# stencil.net
KiCad netlist of a schematic drawn in EAGLE
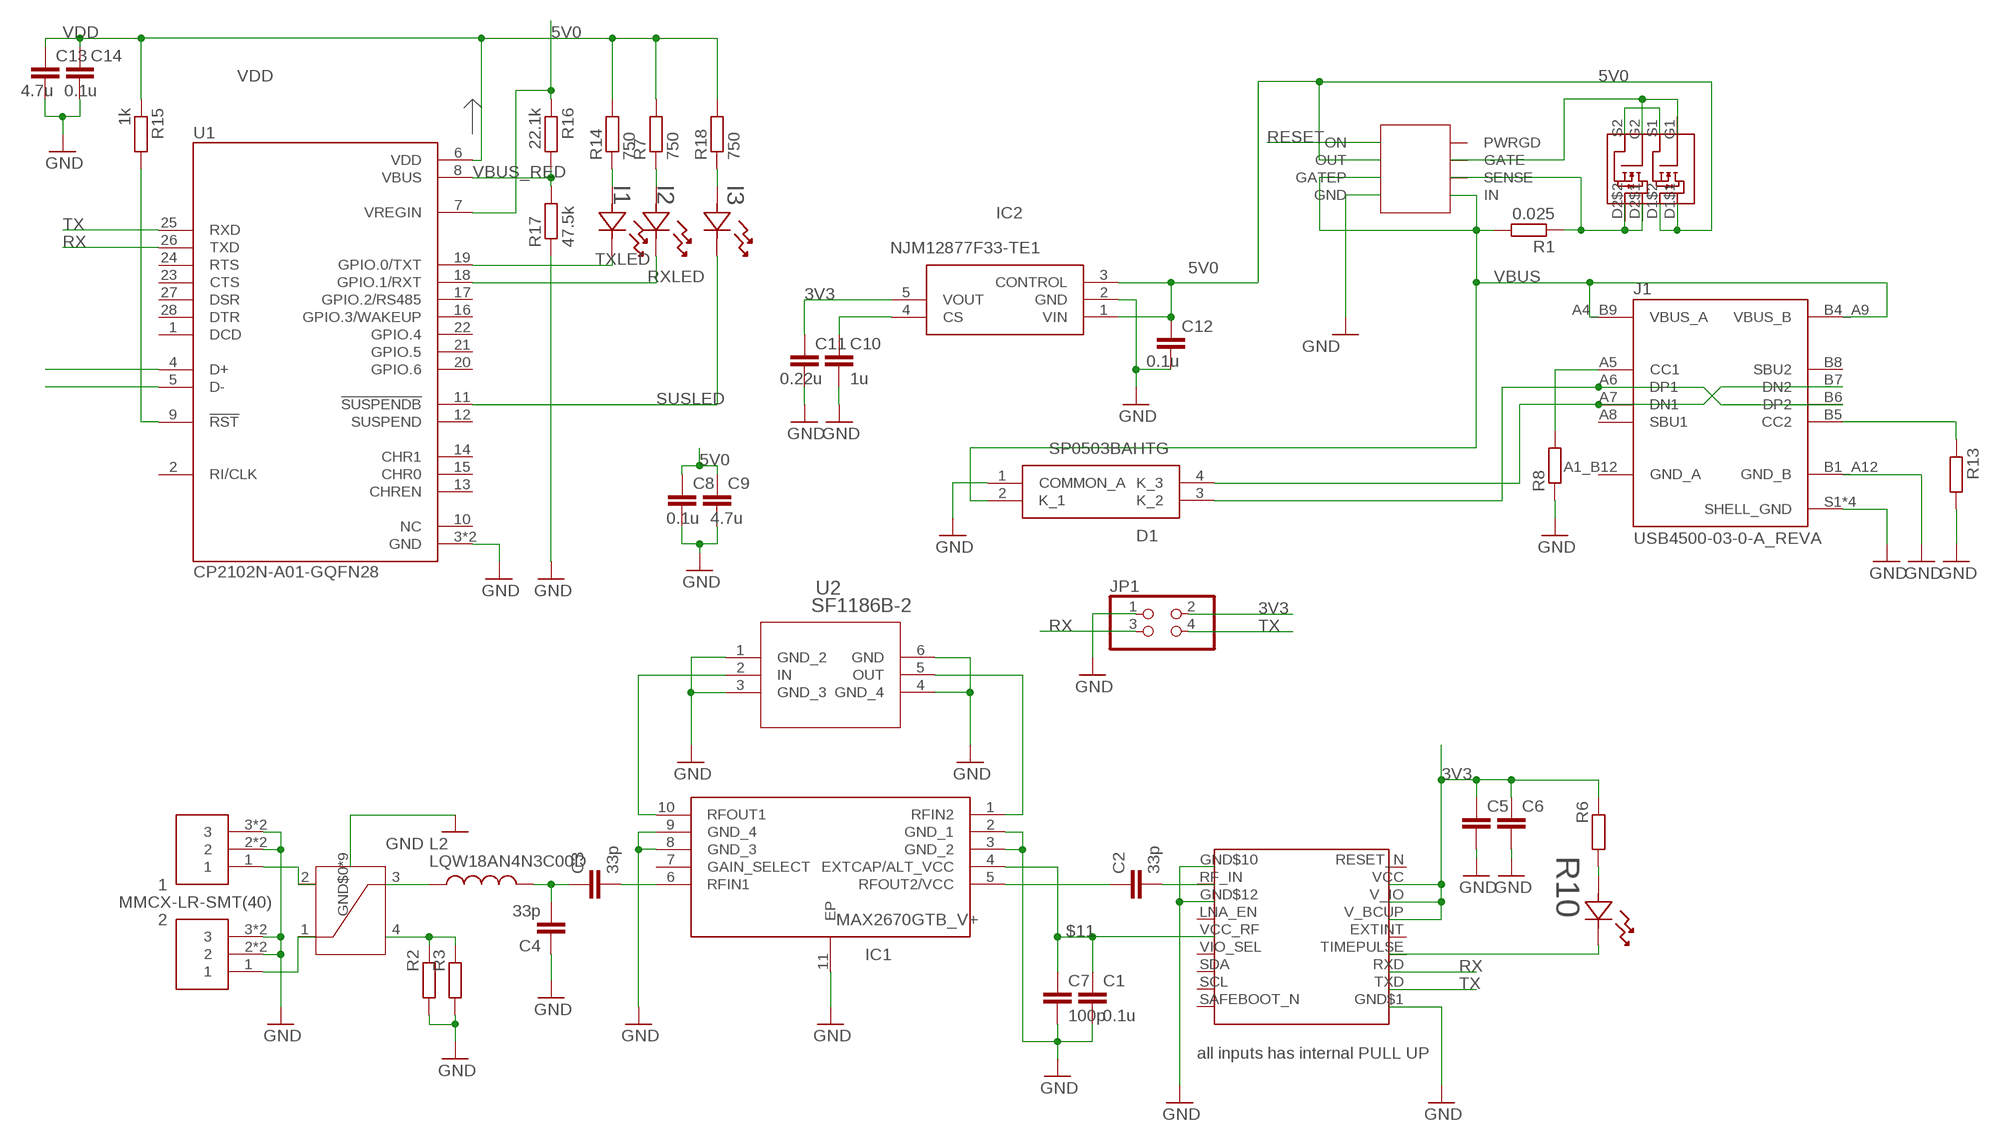
[diagram p0: schematic, sheet 1]
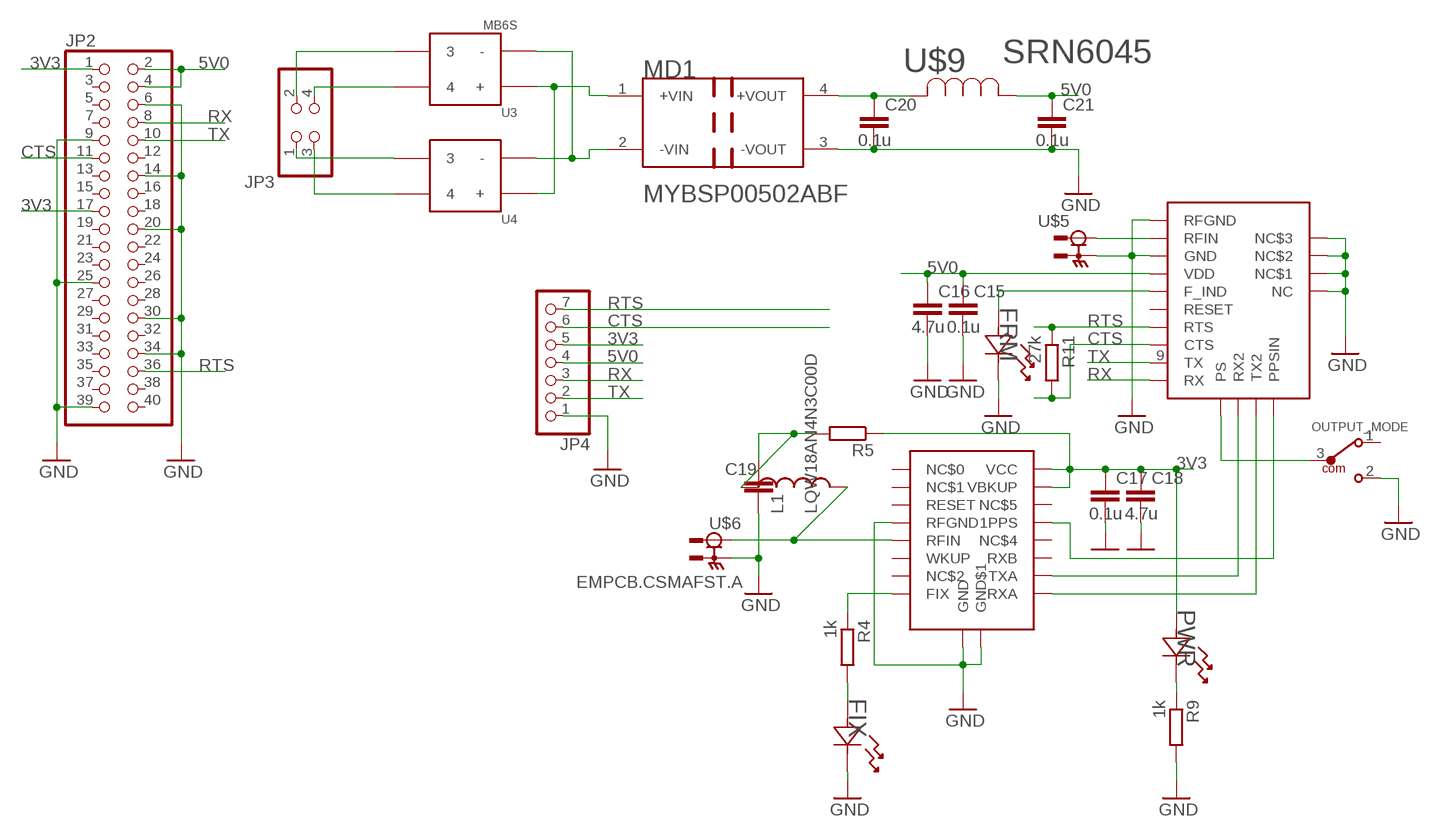
[diagram p1: schematic, sheet 2]

(export (version "E")
  (design (tool "Eeschema 10.0.6"))
  (components
    (comp (ref "C15")
      (value "0.1u")
      (footprint "eagle-import:C1608")
      (libsource (lib "eagle-import") (part "C-EUC1608"))
    )
    (comp (ref "C16")
      (value "4.7u")
      (footprint "eagle-import:C1608")
      (libsource (lib "eagle-import") (part "C-EUC1608"))
    )
    (comp (ref "C17")
      (value "0.1u")
      (footprint "eagle-import:C1608")
      (libsource (lib "eagle-import") (part "C-EUC1608"))
    )
    (comp (ref "C18")
      (value "4.7u")
      (footprint "eagle-import:C1608")
      (libsource (lib "eagle-import") (part "C-EUC1608"))
    )
    (comp (ref "C19")
      (value "C-EUC1608")
      (footprint "eagle-import:C1608")
      (libsource (lib "eagle-import") (part "C-EUC1608"))
    )
    (comp (ref "C20")
      (value "0.1u")
      (footprint "eagle-import:C1608")
      (libsource (lib "eagle-import") (part "C-EUC1608"))
    )
    (comp (ref "C21")
      (value "0.1u")
      (footprint "eagle-import:C1608")
      (libsource (lib "eagle-import") (part "C-EUC1608"))
    )
    (comp (ref "FIX")
      (value "SML-E12P8WT86")
      (footprint "eagle-import:LED_SMLD12_ROM")
      (fields (field (name "COPYRIGHT") "Copyright (C) 2023 Ultra Librarian. All rights reserved."))
      (libsource (lib "eagle-import") (part "SML-E12P8WT86"))
    )
    (comp (ref "FRM")
      (value "SML-E12P8WT86")
      (footprint "eagle-import:LED_SMLD12_ROM")
      (fields (field (name "COPYRIGHT") "Copyright (C) 2023 Ultra Librarian. All rights reserved."))
      (libsource (lib "eagle-import") (part "SML-E12P8WT86"))
    )
    (comp (ref "JP2")
      (value "PINHD-2X20")
      (footprint "eagle-import:2X20")
      (libsource (lib "eagle-import") (part "PINHD-2X20"))
    )
    (comp (ref "JP3")
      (value "PINHD-2X2")
      (footprint "eagle-import:2X02")
      (libsource (lib "eagle-import") (part "PINHD-2X2"))
    )
    (comp (ref "JP4")
      (value "PINHD-1X7/90")
      (footprint "eagle-import:1X07_90")
      (libsource (lib "eagle-import") (part "PINHD-1X7/90"))
    )
    (comp (ref "L1")
      (value "LQW18AN4N3C00D")
      (footprint "eagle-import:INDC1608X100N")
      (fields (field (name "DIGIKEY_PART_NUMBER") "490-6896-2-ND") (field (name "MF") "Murata"))
      (libsource (lib "eagle-import") (part "LQW18AN4N3C00D"))
    )
    (comp (ref "MD1")
      (value "MURATA_MYBSP00502ABFMURATA_MYBSP00502ABF_0_0")
      (footprint "eagle-import:MURATA_MYBSP00502ABF_0")
      (fields (field (name "MF") "Murata Power Solutions Inc.") (field (name "MP") "MYBSP00502ABF"))
      (libsource (lib "eagle-import") (part "MURATA_MYBSP00502ABFMURATA_MYBSP00502ABF_0_0"))
    )
    (comp (ref "OUTPUT_MODE")
      (value "450405020524")
      (footprint "eagle-import:450405020524")
      (libsource (lib "eagle-import") (part "450405020524"))
    )
    (comp (ref "PWR")
      (value "SML-E12P8WT86")
      (footprint "eagle-import:LED_SMLD12_ROM")
      (fields (field (name "COPYRIGHT") "Copyright (C) 2023 Ultra Librarian. All rights reserved."))
      (libsource (lib "eagle-import") (part "SML-E12P8WT86"))
    )
    (comp (ref "R4")
      (value "1k")
      (footprint "eagle-import:R0603")
      (libsource (lib "eagle-import") (part "R-EU_R0603"))
    )
    (comp (ref "R5")
      (value "R-EU_R0603")
      (footprint "eagle-import:R0603")
      (libsource (lib "eagle-import") (part "R-EU_R0603"))
    )
    (comp (ref "R9")
      (value "1k")
      (footprint "eagle-import:R0603")
      (libsource (lib "eagle-import") (part "R-EU_R0603"))
    )
    (comp (ref "R11")
      (value "27k")
      (footprint "eagle-import:R0603_NOSILK")
      (libsource (lib "eagle-import") (part "R-EU_R0603_NOSILK"))
    )
    (comp (ref "U$2")
      (value "GNS5894T")
      (footprint "eagle-import:GNS5XXX")
      (libsource (lib "eagle-import") (part "GNS5894T"))
    )
    (comp (ref "U$4")
      (value "GNS3303")
      (footprint "eagle-import:GNS3303")
      (libsource (lib "eagle-import") (part "GNS3303"))
    )
    (comp (ref "U$5")
      (value "EMPCB.CSMAFST.A")
      (footprint "eagle-import:EMPCB.CSMAFST.A")
      (libsource (lib "eagle-import") (part "EMPCB.CSMAFST.A"))
    )
    (comp (ref "U$6")
      (value "EMPCB.CSMAFST.A")
      (footprint "eagle-import:EMPCB.CSMAFST.A")
      (libsource (lib "eagle-import") (part "EMPCB.CSMAFST.A"))
    )
    (comp (ref "U$9")
      (value "SRN6045")
      (footprint "eagle-import:IND_BOURNS_SRN6045")
      (libsource (lib "eagle-import") (part "SRN6045"))
    )
    (comp (ref "U3")
      (value "MB6S")
      (footprint "eagle-import:SOIC245P670X270-4N")
      (fields (field (name "MF") "onsemi"))
      (libsource (lib "eagle-import") (part "MB6S"))
    )
    (comp (ref "U4")
      (value "MB6S")
      (footprint "eagle-import:SOIC245P670X270-4N")
      (fields (field (name "MF") "onsemi"))
      (libsource (lib "eagle-import") (part "MB6S"))
    )
    (comp (ref "1")
      (value "MMCX-LR-SMT(40)")
      (footprint "eagle-import:MMCX-LR-SMT(40)")
      (libsource (lib "eagle-import") (part "MMCX-LR-SMT(40)"))
    )
    (comp (ref "2")
      (value "MMCX-LR-SMT(40)")
      (footprint "eagle-import:MMCX-LR-SMT(40)")
      (libsource (lib "eagle-import") (part "MMCX-LR-SMT(40)"))
    )
    (comp (ref "C1")
      (value "0.1u")
      (footprint "eagle-import:C1608")
      (libsource (lib "eagle-import") (part "C-EUC1608"))
    )
    (comp (ref "C2")
      (value "33p")
      (footprint "eagle-import:C1608")
      (libsource (lib "eagle-import") (part "C-EUC1608"))
    )
    (comp (ref "C3")
      (value "33p")
      (footprint "eagle-import:C1608")
      (libsource (lib "eagle-import") (part "C-EUC1608"))
    )
    (comp (ref "C4")
      (value "33p")
      (footprint "eagle-import:C1608")
      (libsource (lib "eagle-import") (part "C-EUC1608"))
    )
    (comp (ref "C5")
      (value "C-EUC1608")
      (footprint "eagle-import:C1608")
      (libsource (lib "eagle-import") (part "C-EUC1608"))
    )
    (comp (ref "C6")
      (value "C-EUC1608")
      (footprint "eagle-import:C1608")
      (libsource (lib "eagle-import") (part "C-EUC1608"))
    )
    (comp (ref "C7")
      (value "100p")
      (footprint "eagle-import:C1608")
      (libsource (lib "eagle-import") (part "C-EUC1608"))
    )
    (comp (ref "C8")
      (value "0.1u")
      (footprint "eagle-import:C1608")
      (libsource (lib "eagle-import") (part "C-EUC1608"))
    )
    (comp (ref "C9")
      (value "4.7u")
      (footprint "eagle-import:C1608")
      (libsource (lib "eagle-import") (part "C-EUC1608"))
    )
    (comp (ref "C10")
      (value "1u")
      (footprint "eagle-import:C1608")
      (libsource (lib "eagle-import") (part "C-EUC1608"))
    )
    (comp (ref "C11")
      (value "0.22u")
      (footprint "eagle-import:C1608")
      (libsource (lib "eagle-import") (part "C-EUC1608"))
    )
    (comp (ref "C12")
      (value "0.1u")
      (footprint "eagle-import:C1608")
      (libsource (lib "eagle-import") (part "C-EUC1608"))
    )
    (comp (ref "C13")
      (value "4.7u")
      (footprint "eagle-import:C1608")
      (libsource (lib "eagle-import") (part "C-EUC1608"))
    )
    (comp (ref "C14")
      (value "0.1u")
      (footprint "eagle-import:C1608")
      (libsource (lib "eagle-import") (part "C-EUC1608"))
    )
    (comp (ref "D1")
      (value "SP0503BAHTG")
      (footprint "eagle-import:SP0503BAHTG")
      (fields (field (name "MOUSER_PART_NUMBER") "576-SP0503BAHTG"))
      (libsource (lib "eagle-import") (part "SP0503BAHTG"))
    )
    (comp (ref "I1")
      (value "SML-E12P8WT86")
      (footprint "eagle-import:LED_SMLD12_ROM")
      (fields (field (name "COPYRIGHT") "Copyright (C) 2023 Ultra Librarian. All rights reserved."))
      (libsource (lib "eagle-import") (part "SML-E12P8WT86"))
    )
    (comp (ref "I2")
      (value "SML-E12P8WT86")
      (footprint "eagle-import:LED_SMLD12_ROM")
      (fields (field (name "COPYRIGHT") "Copyright (C) 2023 Ultra Librarian. All rights reserved."))
      (libsource (lib "eagle-import") (part "SML-E12P8WT86"))
    )
    (comp (ref "I3")
      (value "SML-E12P8WT86")
      (footprint "eagle-import:LED_SMLD12_ROM")
      (fields (field (name "COPYRIGHT") "Copyright (C) 2023 Ultra Librarian. All rights reserved."))
      (libsource (lib "eagle-import") (part "SML-E12P8WT86"))
    )
    (comp (ref "IC1")
      (value "MAX2670GTB_V+")
      (footprint "eagle-import:SON50P300X300X80-11N")
      (fields
        (field (name "MANUFACTURER_PART_NUMBER") "MAX2670GTB/V+")
        (field (name "MOUSER_PART_NUMBER") "700-MAX2670GTB/V+")
      )
      (libsource (lib "eagle-import") (part "MAX2670GTB_V+"))
    )
    (comp (ref "IC2")
      (value "NJM12877F33-TE1")
      (footprint "eagle-import:SOT95P280X120-5N")
      (fields (field (name "MOUSER_PART_NUMBER") "513-NJM12877F33-TE1"))
      (libsource (lib "eagle-import") (part "NJM12877F33-TE1"))
    )
    (comp (ref "J1")
      (value "USB4500-03-0-A_REVA")
      (footprint "eagle-import:GCT_USB4500-03-0-A_REVA")
      (fields
        (field (name "DIGI-KEY_PART_NUMBER") "2073-USB4500-03-0-ATR-ND")
        (field (name "MF") "Global Connector Technology")
        (field (name "MP") "USB4500-03-0-A")
      )
      (libsource (lib "eagle-import") (part "USB4500-03-0-A_REVA"))
    )
    (comp (ref "JP1")
      (value "PINHD-2X2")
      (footprint "eagle-import:2X02")
      (libsource (lib "eagle-import") (part "PINHD-2X2"))
    )
    (comp (ref "L2")
      (value "LQW18AN4N3C00D")
      (footprint "eagle-import:INDC1608X100N")
      (fields (field (name "DIGIKEY_PART_NUMBER") "490-6896-2-ND") (field (name "MF") "Murata"))
      (libsource (lib "eagle-import") (part "LQW18AN4N3C00D"))
    )
    (comp (ref "R1")
      (value "0.025")
      (footprint "eagle-import:R0603")
      (libsource (lib "eagle-import") (part "R-EU_R0603"))
    )
    (comp (ref "R2")
      (value "R-EU_R0603")
      (footprint "eagle-import:R0603")
      (libsource (lib "eagle-import") (part "R-EU_R0603"))
    )
    (comp (ref "R3")
      (value "R-EU_R0603")
      (footprint "eagle-import:R0603")
      (libsource (lib "eagle-import") (part "R-EU_R0603"))
    )
    (comp (ref "R6")
      (value "R-EU_R0603")
      (footprint "eagle-import:R0603")
      (libsource (lib "eagle-import") (part "R-EU_R0603"))
    )
    (comp (ref "R7")
      (value "750")
      (footprint "eagle-import:R0603")
      (libsource (lib "eagle-import") (part "R-EU_R0603"))
    )
    (comp (ref "R8")
      (value "R-EU_R0603")
      (footprint "eagle-import:R0603")
      (libsource (lib "eagle-import") (part "R-EU_R0603"))
    )
    (comp (ref "R10")
      (value "SML-E12P8WT86")
      (footprint "eagle-import:LED_SMLD12_ROM")
      (fields (field (name "COPYRIGHT") "Copyright (C) 2023 Ultra Librarian. All rights reserved."))
      (libsource (lib "eagle-import") (part "SML-E12P8WT86"))
    )
    (comp (ref "R13")
      (value "R-EU_R0603")
      (footprint "eagle-import:R0603")
      (libsource (lib "eagle-import") (part "R-EU_R0603"))
    )
    (comp (ref "R14")
      (value "750")
      (footprint "eagle-import:R0603")
      (libsource (lib "eagle-import") (part "R-EU_R0603"))
    )
    (comp (ref "R15")
      (value "1k")
      (footprint "eagle-import:R0603")
      (libsource (lib "eagle-import") (part "R-EU_R0603"))
    )
    (comp (ref "R16")
      (value "22.1k")
      (footprint "eagle-import:R0603")
      (libsource (lib "eagle-import") (part "R-EU_R0603"))
    )
    (comp (ref "R17")
      (value "47.5k")
      (footprint "eagle-import:R0603")
      (libsource (lib "eagle-import") (part "R-EU_R0603"))
    )
    (comp (ref "R18")
      (value "750")
      (footprint "eagle-import:R0603")
      (libsource (lib "eagle-import") (part "R-EU_R0603"))
    )
    (comp (ref "U$1")
      (value "MAX_M10S")
      (footprint "eagle-import:MAX-M10S")
      (libsource (lib "eagle-import") (part "MAX_M10S"))
    )
    (comp (ref "U$3")
      (value "HC125.A")
      (footprint "eagle-import:HC125.A")
      (libsource (lib "eagle-import") (part "HC125.A"))
    )
    (comp (ref "U$7")
      (value "DMG6898LSD")
      (footprint "eagle-import:SOIC127P600X150-8N")
      (libsource (lib "eagle-import") (part "DMG6898LSD"))
    )
    (comp (ref "U$8")
      (value "LTC4361")
      (footprint "eagle-import:SOP65P280X100-8N")
      (libsource (lib "eagle-import") (part "LTC4361"))
    )
    (comp (ref "U1")
      (value "CP2102N-A01-GQFN28")
      (footprint "eagle-import:QFN50P500X500X80-29N")
      (fields (field (name "MF") "Silicon Labs"))
      (libsource (lib "eagle-import") (part "CP2102N-A01-GQFN28"))
    )
    (comp (ref "U2")
      (value "SF1186B-2")
      (footprint "eagle-import:SM3030_MUR")
      (fields (field (name "COPYRIGHT") "Copyright (C) 2023 Ultra Librarian. All rights reserved."))
      (libsource (lib "eagle-import") (part "SF1186B-2"))
    )
  )
  (nets
    (net (code "1") (name "$11") (class "Default")
      (node (ref "C1") (pin "1") (pinfunction "1_1") (pintype "passive"))
      (node (ref "C7") (pin "1") (pinfunction "1_1") (pintype "passive"))
      (node (ref "IC1") (pin "4") (pinfunction "EXTCAP/ALT_VCC_4") (pintype "bidirectional"))
      (node (ref "U$1") (pin "VCC_RF") (pinfunction "VCC_RF_VCC_RF") (pintype "bidirectional"))
    )
    (net (code "2") (name "3V3") (class "Default")
      (node (ref "C11") (pin "1") (pinfunction "1_1") (pintype "passive"))
      (node (ref "C17") (pin "1") (pinfunction "1_1") (pintype "passive"))
      (node (ref "C18") (pin "1") (pinfunction "1_1") (pintype "passive"))
      (node (ref "C5") (pin "1") (pinfunction "1_1") (pintype "passive"))
      (node (ref "C6") (pin "1") (pinfunction "1_1") (pintype "passive"))
      (node (ref "IC2") (pin "5") (pinfunction "VOUT_5") (pintype "bidirectional"))
      (node (ref "JP1") (pin "2") (pinfunction "2_2") (pintype "passive"))
      (node (ref "JP2") (pin "1") (pinfunction "1_1") (pintype "passive"))
      (node (ref "JP2") (pin "17") (pinfunction "17_17") (pintype "passive"))
      (node (ref "JP4") (pin "5") (pinfunction "5_5") (pintype "passive"))
      (node (ref "PWR") (pin "2") (pinfunction "2_2") (pintype "passive"))
      (node (ref "R5") (pin "1") (pinfunction "1_1") (pintype "passive"))
      (node (ref "R6") (pin "2") (pinfunction "2_2") (pintype "passive"))
      (node (ref "U$1") (pin "VCC") (pinfunction "VCC_VCC") (pintype "bidirectional"))
      (node (ref "U$1") (pin "V_BCUP") (pinfunction "V_BCKP_V_BCUP") (pintype "bidirectional"))
      (node (ref "U$1") (pin "V_IO") (pinfunction "V_IO_V_IO") (pintype "bidirectional"))
      (node (ref "U$4") (pin "15") (pinfunction "VBKUP_15") (pintype "bidirectional"))
      (node (ref "U$4") (pin "16") (pinfunction "VCC_16") (pintype "bidirectional"))
    )
    (net (code "3") (name "5V0") (class "Default")
      (node (ref "C12") (pin "1") (pinfunction "1_1") (pintype "passive"))
      (node (ref "C15") (pin "1") (pinfunction "1_1") (pintype "passive"))
      (node (ref "C16") (pin "1") (pinfunction "1_1") (pintype "passive"))
      (node (ref "C21") (pin "1") (pinfunction "1_1") (pintype "passive"))
      (node (ref "C8") (pin "1") (pinfunction "1_1") (pintype "passive"))
      (node (ref "C9") (pin "1") (pinfunction "1_1") (pintype "passive"))
      (node (ref "IC2") (pin "1") (pinfunction "VIN_1") (pintype "bidirectional"))
      (node (ref "IC2") (pin "3") (pinfunction "CONTROL_3") (pintype "bidirectional"))
      (node (ref "JP2") (pin "2") (pinfunction "2_2") (pintype "passive"))
      (node (ref "JP2") (pin "4") (pinfunction "4_4") (pintype "passive"))
      (node (ref "JP4") (pin "4") (pinfunction "4_4") (pintype "passive"))
      (node (ref "R16") (pin "1") (pinfunction "1_1") (pintype "passive"))
      (node (ref "U$2") (pin "4") (pinfunction "VDD_4") (pintype "bidirectional"))
      (node (ref "U$7") (pin "D1$1") (pinfunction "D1$1_D1$1") (pintype "bidirectional"))
      (node (ref "U$7") (pin "D1$2") (pinfunction "D1$2_D1$2") (pintype "bidirectional"))
      (node (ref "U$8") (pin "OUT") (pinfunction "OUT_OUT") (pintype "bidirectional"))
      (node (ref "U$9") (pin "1") (pinfunction "1_1") (pintype "passive"))
      (node (ref "U1") (pin "7") (pinfunction "VREGIN_7") (pintype "power_in"))
    )
    (net (code "4") (name "CTS") (class "Default")
      (node (ref "JP2") (pin "11") (pinfunction "11_11") (pintype "passive"))
      (node (ref "JP4") (pin "6") (pinfunction "6_6") (pintype "passive"))
      (node (ref "R11") (pin "2") (pinfunction "2_2") (pintype "passive"))
      (node (ref "U$2") (pin "8") (pinfunction "CTS_8") (pintype "bidirectional"))
    )
    (net (code "5") (name "D+") (class "Default")
      (node (ref "D1") (pin "3") (pinfunction "K_2_3") (pintype "bidirectional"))
      (node (ref "J1") (pin "A6") (pinfunction "DP1_A6") (pintype "bidirectional"))
      (node (ref "J1") (pin "B6") (pinfunction "DP2_B6") (pintype "bidirectional"))
      (node (ref "U1") (pin "4") (pinfunction "D+_4") (pintype "bidirectional"))
    )
    (net (code "6") (name "D-") (class "Default")
      (node (ref "D1") (pin "4") (pinfunction "K_3_4") (pintype "bidirectional"))
      (node (ref "J1") (pin "A7") (pinfunction "DN1_A7") (pintype "bidirectional"))
      (node (ref "J1") (pin "B7") (pinfunction "DN2_B7") (pintype "bidirectional"))
      (node (ref "U1") (pin "5") (pinfunction "D-_5") (pintype "bidirectional"))
    )
    (net (code "7") (name "GND") (class "Default")
      (node (ref "1") (pin "2") (pinfunction "2_2") (pintype "bidirectional"))
      (node (ref "1") (pin "3") (pinfunction "3_3") (pintype "bidirectional"))
      (node (ref "1") (pin "4") (pinfunction "2_4") (pintype "bidirectional"))
      (node (ref "1") (pin "5") (pinfunction "3_5") (pintype "bidirectional"))
      (node (ref "2") (pin "2") (pinfunction "2_2") (pintype "bidirectional"))
      (node (ref "2") (pin "3") (pinfunction "3_3") (pintype "bidirectional"))
      (node (ref "2") (pin "4") (pinfunction "2_4") (pintype "bidirectional"))
      (node (ref "2") (pin "5") (pinfunction "3_5") (pintype "bidirectional"))
      (node (ref "C1") (pin "2") (pinfunction "2_2") (pintype "passive"))
      (node (ref "C10") (pin "2") (pinfunction "2_2") (pintype "passive"))
      (node (ref "C11") (pin "2") (pinfunction "2_2") (pintype "passive"))
      (node (ref "C12") (pin "2") (pinfunction "2_2") (pintype "passive"))
      (node (ref "C13") (pin "2") (pinfunction "2_2") (pintype "passive"))
      (node (ref "C14") (pin "2") (pinfunction "2_2") (pintype "passive"))
      (node (ref "C15") (pin "2") (pinfunction "2_2") (pintype "passive"))
      (node (ref "C16") (pin "2") (pinfunction "2_2") (pintype "passive"))
      (node (ref "C17") (pin "2") (pinfunction "2_2") (pintype "passive"))
      (node (ref "C18") (pin "2") (pinfunction "2_2") (pintype "passive"))
      (node (ref "C19") (pin "2") (pinfunction "2_2") (pintype "passive"))
      (node (ref "C20") (pin "2") (pinfunction "2_2") (pintype "passive"))
      (node (ref "C21") (pin "2") (pinfunction "2_2") (pintype "passive"))
      (node (ref "C4") (pin "1") (pinfunction "1_1") (pintype "passive"))
      (node (ref "C5") (pin "2") (pinfunction "2_2") (pintype "passive"))
      (node (ref "C6") (pin "2") (pinfunction "2_2") (pintype "passive"))
      (node (ref "C7") (pin "2") (pinfunction "2_2") (pintype "passive"))
      (node (ref "C8") (pin "2") (pinfunction "2_2") (pintype "passive"))
      (node (ref "C9") (pin "2") (pinfunction "2_2") (pintype "passive"))
      (node (ref "D1") (pin "1") (pinfunction "COMMON_A_1") (pintype "bidirectional"))
      (node (ref "FIX") (pin "1") (pinfunction "1_1") (pintype "passive"))
      (node (ref "FRM") (pin "1") (pinfunction "1_1") (pintype "passive"))
      (node (ref "IC1") (pin "11") (pinfunction "EP_11") (pintype "bidirectional"))
      (node (ref "IC1") (pin "2") (pinfunction "GND_1_2") (pintype "bidirectional"))
      (node (ref "IC1") (pin "3") (pinfunction "GND_2_3") (pintype "bidirectional"))
      (node (ref "IC1") (pin "8") (pinfunction "GND_3_8") (pintype "bidirectional"))
      (node (ref "IC1") (pin "9") (pinfunction "GND_4_9") (pintype "bidirectional"))
      (node (ref "IC2") (pin "2") (pinfunction "GND_2") (pintype "bidirectional"))
      (node (ref "J1") (pin "B1_A12") (pinfunction "GND_B_B1_A12") (pintype "power_in"))
      (node (ref "J1") (pin "S1") (pinfunction "SHELL_GND_S1") (pintype "power_in"))
      (node (ref "J1") (pin "S2") (pinfunction "SHELL_GND_S2") (pintype "power_in"))
      (node (ref "J1") (pin "S3") (pinfunction "SHELL_GND_S3") (pintype "power_in"))
      (node (ref "J1") (pin "S4") (pinfunction "SHELL_GND_S4") (pintype "power_in"))
      (node (ref "JP1") (pin "1") (pinfunction "1_1") (pintype "passive"))
      (node (ref "JP2") (pin "14") (pinfunction "14_14") (pintype "passive"))
      (node (ref "JP2") (pin "20") (pinfunction "20_20") (pintype "passive"))
      (node (ref "JP2") (pin "25") (pinfunction "25_25") (pintype "passive"))
      (node (ref "JP2") (pin "30") (pinfunction "30_30") (pintype "passive"))
      (node (ref "JP2") (pin "34") (pinfunction "34_34") (pintype "passive"))
      (node (ref "JP2") (pin "39") (pinfunction "39_39") (pintype "passive"))
      (node (ref "JP2") (pin "6") (pinfunction "6_6") (pintype "passive"))
      (node (ref "JP2") (pin "9") (pinfunction "9_9") (pintype "passive"))
      (node (ref "JP4") (pin "1") (pinfunction "1_1") (pintype "passive"))
      (node (ref "MD1") (pin "3") (pinfunction "-VOUT_3") (pintype "power_in"))
      (node (ref "OUTPUT_MODE") (pin "2") (pinfunction "3_2") (pintype "passive"))
      (node (ref "R13") (pin "2") (pinfunction "2_2") (pintype "passive"))
      (node (ref "R17") (pin "1") (pinfunction "1_1") (pintype "passive"))
      (node (ref "R2") (pin "1") (pinfunction "1_1") (pintype "passive"))
      (node (ref "R3") (pin "1") (pinfunction "1_1") (pintype "passive"))
      (node (ref "R8") (pin "1") (pinfunction "1_1") (pintype "passive"))
      (node (ref "R9") (pin "2") (pinfunction "2_2") (pintype "passive"))
      (node (ref "U$1") (pin "GND$1") (pinfunction "GND$1_GND$1") (pintype "bidirectional"))
      (node (ref "U$1") (pin "GND$10") (pinfunction "GND$10_GND$10") (pintype "bidirectional"))
      (node (ref "U$1") (pin "GND$12") (pinfunction "GND$12_GND$12") (pintype "bidirectional"))
      (node (ref "U$2") (pin "1") (pinfunction "RFGND_1") (pintype "bidirectional"))
      (node (ref "U$2") (pin "15") (pinfunction "NC_15") (pintype "bidirectional"))
      (node (ref "U$2") (pin "16") (pinfunction "NC$1_16") (pintype "bidirectional"))
      (node (ref "U$2") (pin "17") (pinfunction "NC$2_17") (pintype "bidirectional"))
      (node (ref "U$2") (pin "18") (pinfunction "NC$3_18") (pintype "bidirectional"))
      (node (ref "U$2") (pin "3") (pinfunction "GND_3") (pintype "bidirectional"))
      (node (ref "U$3") (pin "GND$0") (pinfunction "GND_GND$0") (pintype "bidirectional"))
      (node (ref "U$3") (pin "GND$1") (pinfunction "GND_GND$1") (pintype "bidirectional"))
      (node (ref "U$3") (pin "GND$2") (pinfunction "GND_GND$2") (pintype "bidirectional"))
      (node (ref "U$3") (pin "GND$3") (pinfunction "GND_GND$3") (pintype "bidirectional"))
      (node (ref "U$3") (pin "GND$4") (pinfunction "GND_GND$4") (pintype "bidirectional"))
      (node (ref "U$3") (pin "GND$5") (pinfunction "GND_GND$5") (pintype "bidirectional"))
      (node (ref "U$3") (pin "GND$6") (pinfunction "GND_GND$6") (pintype "bidirectional"))
      (node (ref "U$3") (pin "GND$7") (pinfunction "GND_GND$7") (pintype "bidirectional"))
      (node (ref "U$3") (pin "GND$8") (pinfunction "GND_GND$8") (pintype "bidirectional"))
      (node (ref "U$4") (pin "4") (pinfunction "RFGND_4") (pintype "bidirectional"))
      (node (ref "U$4") (pin "E1") (pinfunction "GND_E1") (pintype "bidirectional"))
      (node (ref "U$4") (pin "E2") (pinfunction "GND$1_E2") (pintype "bidirectional"))
      (node (ref "U$5") (pin "GND$0") (pinfunction "2_GND$0") (pintype "passive"))
      (node (ref "U$5") (pin "GND$1") (pinfunction "2_GND$1") (pintype "passive"))
      (node (ref "U$5") (pin "GND$2") (pinfunction "2_GND$2") (pintype "passive"))
      (node (ref "U$5") (pin "GND$3") (pinfunction "2_GND$3") (pintype "passive"))
      (node (ref "U$6") (pin "GND$0") (pinfunction "2_GND$0") (pintype "passive"))
      (node (ref "U$6") (pin "GND$1") (pinfunction "2_GND$1") (pintype "passive"))
      (node (ref "U$6") (pin "GND$2") (pinfunction "2_GND$2") (pintype "passive"))
      (node (ref "U$6") (pin "GND$3") (pinfunction "2_GND$3") (pintype "passive"))
      (node (ref "U$8") (pin "GND") (pinfunction "GND_GND") (pintype "bidirectional"))
      (node (ref "U1") (pin "29") (pinfunction "GND_29") (pintype "power_in"))
      (node (ref "U1") (pin "3") (pinfunction "GND_3") (pintype "power_in"))
      (node (ref "U2") (pin "1") (pinfunction "GND_2_1") (pintype "passive"))
      (node (ref "U2") (pin "3") (pinfunction "GND_3_3") (pintype "passive"))
      (node (ref "U2") (pin "4") (pinfunction "GND_4_4") (pintype "passive"))
      (node (ref "U2") (pin "6") (pinfunction "GND_6") (pintype "passive"))
    )
    (net (code "8") (name "GND_A") (class "Default")
      (node (ref "J1") (pin "A1_B12") (pinfunction "GND_A_A1_B12") (pintype "power_in"))
    )
    (net (code "9") (name "Net-(1-Pad1)") (class "Default")
      (node (ref "1") (pin "1") (pinfunction "1_1") (pintype "bidirectional"))
      (node (ref "U$3") (pin "2") (pinfunction "2_2") (pintype "bidirectional"))
    )
    (net (code "10") (name "Net-(2-Pad1)") (class "Default")
      (node (ref "2") (pin "1") (pinfunction "1_1") (pintype "bidirectional"))
      (node (ref "U$3") (pin "1") (pinfunction "1_1") (pintype "bidirectional"))
    )
    (net (code "11") (name "Net-(C2-Pad2)") (class "Default")
      (node (ref "C2") (pin "2") (pinfunction "2_2") (pintype "passive"))
      (node (ref "U$1") (pin "RF_IN") (pinfunction "RF_IN_RF_IN") (pintype "bidirectional"))
    )
    (net (code "12") (name "Net-(C3-Pad1)") (class "Default")
      (node (ref "C3") (pin "1") (pinfunction "1_1") (pintype "passive"))
      (node (ref "C4") (pin "2") (pinfunction "2_2") (pintype "passive"))
      (node (ref "L2") (pin "2") (pinfunction "2_2") (pintype "passive"))
    )
    (net (code "13") (name "Net-(C19-Pad1)") (class "Default")
      (node (ref "C19") (pin "1") (pinfunction "1_1") (pintype "passive"))
      (node (ref "L1") (pin "1") (pinfunction "1_1") (pintype "passive"))
      (node (ref "R5") (pin "2") (pinfunction "2_2") (pintype "passive"))
    )
    (net (code "14") (name "Net-(FIX-Pad2)") (class "Default")
      (node (ref "FIX") (pin "2") (pinfunction "2_2") (pintype "passive"))
      (node (ref "R4") (pin "2") (pinfunction "2_2") (pintype "passive"))
    )
    (net (code "15") (name "Net-(I1-Pad2)") (class "Default")
      (node (ref "I1") (pin "2") (pinfunction "2_2") (pintype "passive"))
      (node (ref "R14") (pin "1") (pinfunction "1_1") (pintype "passive"))
    )
    (net (code "16") (name "Net-(I2-Pad2)") (class "Default")
      (node (ref "I2") (pin "2") (pinfunction "2_2") (pintype "passive"))
      (node (ref "R7") (pin "1") (pinfunction "1_1") (pintype "passive"))
    )
    (net (code "17") (name "Net-(I3-Pad2)") (class "Default")
      (node (ref "I3") (pin "2") (pinfunction "2_2") (pintype "passive"))
      (node (ref "R18") (pin "1") (pinfunction "1_1") (pintype "passive"))
    )
    (net (code "18") (name "Net-(IC1-RFIN1)") (class "Default")
      (node (ref "C3") (pin "2") (pinfunction "2_2") (pintype "passive"))
      (node (ref "IC1") (pin "6") (pinfunction "RFIN1_6") (pintype "bidirectional"))
    )
    (net (code "19") (name "Net-(IC1-RFIN2)") (class "Default")
      (node (ref "IC1") (pin "1") (pinfunction "RFIN2_1") (pintype "bidirectional"))
      (node (ref "U2") (pin "5") (pinfunction "OUT_5") (pintype "output"))
    )
    (net (code "20") (name "Net-(IC1-RFOUT1)") (class "Default")
      (node (ref "IC1") (pin "10") (pinfunction "RFOUT1_10") (pintype "bidirectional"))
      (node (ref "U2") (pin "2") (pinfunction "IN_2") (pintype "input"))
    )
    (net (code "21") (name "Net-(IC1-RFOUT2{slash}VCC)") (class "Default")
      (node (ref "C2") (pin "1") (pinfunction "1_1") (pintype "passive"))
      (node (ref "IC1") (pin "5") (pinfunction "RFOUT2/VCC_5") (pintype "bidirectional"))
    )
    (net (code "22") (name "Net-(IC2-CS)") (class "Default")
      (node (ref "C10") (pin "1") (pinfunction "1_1") (pintype "passive"))
      (node (ref "IC2") (pin "4") (pinfunction "CS_4") (pintype "bidirectional"))
    )
    (net (code "23") (name "Net-(J1-CC1)") (class "Default")
      (node (ref "J1") (pin "A5") (pinfunction "CC1_A5") (pintype "bidirectional"))
      (node (ref "R8") (pin "2") (pinfunction "2_2") (pintype "passive"))
    )
    (net (code "24") (name "Net-(J1-CC2)") (class "Default")
      (node (ref "J1") (pin "B5") (pinfunction "CC2_B5") (pintype "bidirectional"))
      (node (ref "R13") (pin "1") (pinfunction "1_1") (pintype "passive"))
    )
    (net (code "25") (name "Net-(JP3-Pad1)") (class "Default")
      (node (ref "JP3") (pin "1") (pinfunction "1_1") (pintype "passive"))
      (node (ref "U4") (pin "3") (pinfunction "3_3") (pintype "output"))
    )
    (net (code "26") (name "Net-(JP3-Pad2)") (class "Default")
      (node (ref "JP3") (pin "2") (pinfunction "2_2") (pintype "passive"))
      (node (ref "U3") (pin "3") (pinfunction "3_3") (pintype "output"))
    )
    (net (code "27") (name "Net-(JP3-Pad3)") (class "Default")
      (node (ref "JP3") (pin "3") (pinfunction "3_3") (pintype "passive"))
      (node (ref "U4") (pin "4") (pinfunction "4_4") (pintype "output"))
    )
    (net (code "28") (name "Net-(JP3-Pad4)") (class "Default")
      (node (ref "JP3") (pin "4") (pinfunction "4_4") (pintype "passive"))
      (node (ref "U3") (pin "4") (pinfunction "4_4") (pintype "output"))
    )
    (net (code "29") (name "Net-(L2-Pad1)") (class "Default")
      (node (ref "L2") (pin "1") (pinfunction "1_1") (pintype "passive"))
      (node (ref "U$3") (pin "3") (pinfunction "3_3") (pintype "bidirectional"))
    )
    (net (code "30") (name "Net-(MD1-+VIN)") (class "Default")
      (node (ref "MD1") (pin "1") (pinfunction "+VIN_1") (pintype "power_in"))
      (node (ref "U3") (pin "1") (pinfunction "+_1") (pintype "input"))
      (node (ref "U4") (pin "1") (pinfunction "+_1") (pintype "input"))
    )
    (net (code "31") (name "Net-(MD1-+VOUT)") (class "Default")
      (node (ref "C20") (pin "1") (pinfunction "1_1") (pintype "passive"))
      (node (ref "MD1") (pin "4") (pinfunction "+VOUT_4") (pintype "power_in"))
      (node (ref "U$9") (pin "2") (pinfunction "2_2") (pintype "passive"))
    )
    (net (code "32") (name "Net-(MD1--VIN)") (class "Default")
      (node (ref "MD1") (pin "2") (pinfunction "-VIN_2") (pintype "power_in"))
      (node (ref "U3") (pin "2") (pinfunction "-_2") (pintype "input"))
      (node (ref "U4") (pin "2") (pinfunction "-_2") (pintype "input"))
    )
    (net (code "33") (name "Net-(OUTPUT_MODE-2)") (class "Default")
      (node (ref "OUTPUT_MODE") (pin "3") (pinfunction "2_3") (pintype "passive"))
      (node (ref "U$2") (pin "11") (pinfunction "PS_11") (pintype "bidirectional"))
    )
    (net (code "34") (name "Net-(PWR-Pad1)") (class "Default")
      (node (ref "PWR") (pin "1") (pinfunction "1_1") (pintype "passive"))
      (node (ref "R9") (pin "1") (pinfunction "1_1") (pintype "passive"))
    )
    (net (code "35") (name "Net-(R1-Pad1)") (class "Default")
      (node (ref "R1") (pin "1") (pinfunction "1_1") (pintype "passive"))
      (node (ref "U$7") (pin "D2$1") (pinfunction "D2$1_D2$1") (pintype "bidirectional"))
      (node (ref "U$7") (pin "D2$2") (pinfunction "D2$2_D2$2") (pintype "bidirectional"))
      (node (ref "U$8") (pin "SENSE") (pinfunction "SENSE_SENSE") (pintype "bidirectional"))
    )
    (net (code "36") (name "Net-(R2-Pad2)") (class "Default")
      (node (ref "R2") (pin "2") (pinfunction "2_2") (pintype "passive"))
      (node (ref "R3") (pin "2") (pinfunction "2_2") (pintype "passive"))
      (node (ref "U$3") (pin "4") (pinfunction "4_4") (pintype "bidirectional"))
    )
    (net (code "37") (name "Net-(R10-Pad1)") (class "Default")
      (node (ref "R10") (pin "1") (pinfunction "1_1") (pintype "passive"))
      (node (ref "U$1") (pin "TIMEPULSE") (pinfunction "TIMEPULSE_TIMEPULSE") (pintype "bidirectional"))
    )
    (net (code "38") (name "Net-(R10-Pad2)") (class "Default")
      (node (ref "R10") (pin "2") (pinfunction "2_2") (pintype "passive"))
      (node (ref "R6") (pin "1") (pinfunction "1_1") (pintype "passive"))
    )
    (net (code "39") (name "Net-(U$2-F_IND)") (class "Default")
      (node (ref "FRM") (pin "2") (pinfunction "2_2") (pintype "passive"))
      (node (ref "U$2") (pin "5") (pinfunction "F_IND_5") (pintype "bidirectional"))
    )
    (net (code "40") (name "Net-(U$2-PPSIN)") (class "Default")
      (node (ref "U$2") (pin "14") (pinfunction "PPSIN_14") (pintype "bidirectional"))
      (node (ref "U$4") (pin "13") (pinfunction "1PPS_13") (pintype "bidirectional"))
    )
    (net (code "41") (name "Net-(U$2-RFIN)") (class "Default")
      (node (ref "U$2") (pin "2") (pinfunction "RFIN_2") (pintype "bidirectional"))
      (node (ref "U$5") (pin "RF") (pinfunction "1_RF") (pintype "passive"))
    )
    (net (code "42") (name "Net-(U$2-RX2)") (class "Default")
      (node (ref "U$2") (pin "12") (pinfunction "RX2_12") (pintype "bidirectional"))
      (node (ref "U$4") (pin "10") (pinfunction "TXA_10") (pintype "bidirectional"))
    )
    (net (code "43") (name "Net-(U$2-TX2)") (class "Default")
      (node (ref "U$2") (pin "13") (pinfunction "TX2_13") (pintype "bidirectional"))
      (node (ref "U$4") (pin "9") (pinfunction "RXA_9") (pintype "bidirectional"))
    )
    (net (code "44") (name "Net-(U$4-FIX)") (class "Default")
      (node (ref "R4") (pin "1") (pinfunction "1_1") (pintype "passive"))
      (node (ref "U$4") (pin "8") (pinfunction "FIX_8") (pintype "bidirectional"))
    )
    (net (code "45") (name "Net-(U$4-RFIN)") (class "Default")
      (node (ref "L1") (pin "2") (pinfunction "2_2") (pintype "passive"))
      (node (ref "U$4") (pin "5") (pinfunction "RFIN_5") (pintype "bidirectional"))
      (node (ref "U$6") (pin "RF") (pinfunction "1_RF") (pintype "passive"))
    )
    (net (code "46") (name "Net-(U$7-PadG1)") (class "Default")
      (node (ref "U$7") (pin "G1") (pinfunction "G1_G1") (pintype "bidirectional"))
      (node (ref "U$7") (pin "G2") (pinfunction "G2_G2") (pintype "bidirectional"))
      (node (ref "U$8") (pin "GATE") (pinfunction "GATE_GATE") (pintype "bidirectional"))
    )
    (net (code "47") (name "Net-(U$7-PadS1)") (class "Default")
      (node (ref "U$7") (pin "S1") (pinfunction "S1_S1") (pintype "bidirectional"))
      (node (ref "U$7") (pin "S2") (pinfunction "S2_S2") (pintype "bidirectional"))
    )
    (net (code "48") (name "Net-(U1-~{RST})") (class "Default")
      (node (ref "R15") (pin "2") (pinfunction "2_2") (pintype "passive"))
      (node (ref "U1") (pin "9") (pinfunction "~{RST}_9") (pintype "input"))
    )
    (net (code "49") (name "RESET") (class "Default")
      (node (ref "U$8") (pin "ON") (pinfunction "ON_ON") (pintype "bidirectional"))
    )
    (net (code "50") (name "RTS") (class "Default")
      (node (ref "JP2") (pin "36") (pinfunction "36_36") (pintype "passive"))
      (node (ref "JP4") (pin "7") (pinfunction "7_7") (pintype "passive"))
      (node (ref "R11") (pin "1") (pinfunction "1_1") (pintype "passive"))
      (node (ref "U$2") (pin "7") (pinfunction "RTS_7") (pintype "bidirectional"))
    )
    (net (code "51") (name "RX") (class "Default")
      (node (ref "JP1") (pin "3") (pinfunction "3_3") (pintype "passive"))
      (node (ref "JP2") (pin "8") (pinfunction "8_8") (pintype "passive"))
      (node (ref "JP4") (pin "3") (pinfunction "3_3") (pintype "passive"))
      (node (ref "U$1") (pin "RXD") (pinfunction "RXD_RXD") (pintype "bidirectional"))
      (node (ref "U$2") (pin "10") (pinfunction "RX_10") (pintype "bidirectional"))
      (node (ref "U1") (pin "26") (pinfunction "TXD_26") (pintype "output"))
    )
    (net (code "52") (name "RXLED") (class "Default")
      (node (ref "I2") (pin "1") (pinfunction "1_1") (pintype "passive"))
      (node (ref "U1") (pin "18") (pinfunction "GPIO.1/RXT_18") (pintype "bidirectional"))
    )
    (net (code "53") (name "SUSLED") (class "Default")
      (node (ref "I3") (pin "1") (pinfunction "1_1") (pintype "passive"))
      (node (ref "U1") (pin "11") (pinfunction "~{SUSPENDB}_11") (pintype "output"))
    )
    (net (code "54") (name "TX") (class "Default")
      (node (ref "JP1") (pin "4") (pinfunction "4_4") (pintype "passive"))
      (node (ref "JP2") (pin "10") (pinfunction "10_10") (pintype "passive"))
      (node (ref "JP4") (pin "2") (pinfunction "2_2") (pintype "passive"))
      (node (ref "U$1") (pin "TXD") (pinfunction "TXD_TXD") (pintype "bidirectional"))
      (node (ref "U$2") (pin "9") (pinfunction "TX_9") (pintype "bidirectional"))
      (node (ref "U1") (pin "25") (pinfunction "RXD_25") (pintype "input"))
    )
    (net (code "55") (name "TXLED") (class "Default")
      (node (ref "I1") (pin "1") (pinfunction "1_1") (pintype "passive"))
      (node (ref "U1") (pin "19") (pinfunction "GPIO.0/TXT_19") (pintype "bidirectional"))
    )
    (net (code "56") (name "VBUS") (class "Default")
      (node (ref "D1") (pin "2") (pinfunction "K_1_2") (pintype "bidirectional"))
      (node (ref "J1") (pin "A4_B9") (pinfunction "VBUS_A_A4_B9") (pintype "power_in"))
      (node (ref "J1") (pin "B4_A9") (pinfunction "VBUS_B_B4_A9") (pintype "power_in"))
      (node (ref "R1") (pin "2") (pinfunction "2_2") (pintype "passive"))
      (node (ref "U$8") (pin "GATEP") (pinfunction "GATEP_GATEP") (pintype "bidirectional"))
      (node (ref "U$8") (pin "IN") (pinfunction "IN_IN") (pintype "bidirectional"))
    )
    (net (code "57") (name "VBUS_RED") (class "Default")
      (node (ref "R16") (pin "2") (pinfunction "2_2") (pintype "passive"))
      (node (ref "R17") (pin "2") (pinfunction "2_2") (pintype "passive"))
      (node (ref "U1") (pin "8") (pinfunction "VBUS_8") (pintype "power_in"))
    )
    (net (code "58") (name "VDD") (class "Default")
      (node (ref "C13") (pin "1") (pinfunction "1_1") (pintype "passive"))
      (node (ref "C14") (pin "1") (pinfunction "1_1") (pintype "passive"))
      (node (ref "R14") (pin "2") (pinfunction "2_2") (pintype "passive"))
      (node (ref "R15") (pin "1") (pinfunction "1_1") (pintype "passive"))
      (node (ref "R18") (pin "2") (pinfunction "2_2") (pintype "passive"))
      (node (ref "R7") (pin "2") (pinfunction "2_2") (pintype "passive"))
      (node (ref "U1") (pin "6") (pinfunction "VDD_6") (pintype "power_in"))
    )
    (net (code "59") (name "unconnected-(IC1-GAIN_SELECT-Pad7)") (class "Default")
      (node (ref "IC1") (pin "7") (pinfunction "GAIN_SELECT_7") (pintype "bidirectional"))
    )
    (net (code "60") (name "unconnected-(J1-SBU1-PadA8)") (class "Default")
      (node (ref "J1") (pin "A8") (pinfunction "SBU1_A8") (pintype "bidirectional"))
    )
    (net (code "61") (name "unconnected-(J1-SBU2-PadB8)") (class "Default")
      (node (ref "J1") (pin "B8") (pinfunction "SBU2_B8") (pintype "bidirectional"))
    )
    (net (code "62") (name "unconnected-(JP2-Pad3)") (class "Default")
      (node (ref "JP2") (pin "3") (pinfunction "3_3") (pintype "passive"))
    )
    (net (code "63") (name "unconnected-(JP2-Pad5)") (class "Default")
      (node (ref "JP2") (pin "5") (pinfunction "5_5") (pintype "passive"))
    )
    (net (code "64") (name "unconnected-(JP2-Pad7)") (class "Default")
      (node (ref "JP2") (pin "7") (pinfunction "7_7") (pintype "passive"))
    )
    (net (code "65") (name "unconnected-(JP2-Pad12)") (class "Default")
      (node (ref "JP2") (pin "12") (pinfunction "12_12") (pintype "passive"))
    )
    (net (code "66") (name "unconnected-(JP2-Pad13)") (class "Default")
      (node (ref "JP2") (pin "13") (pinfunction "13_13") (pintype "passive"))
    )
    (net (code "67") (name "unconnected-(JP2-Pad15)") (class "Default")
      (node (ref "JP2") (pin "15") (pinfunction "15_15") (pintype "passive"))
    )
    (net (code "68") (name "unconnected-(JP2-Pad16)") (class "Default")
      (node (ref "JP2") (pin "16") (pinfunction "16_16") (pintype "passive"))
    )
    (net (code "69") (name "unconnected-(JP2-Pad18)") (class "Default")
      (node (ref "JP2") (pin "18") (pinfunction "18_18") (pintype "passive"))
    )
    (net (code "70") (name "unconnected-(JP2-Pad19)") (class "Default")
      (node (ref "JP2") (pin "19") (pinfunction "19_19") (pintype "passive"))
    )
    (net (code "71") (name "unconnected-(JP2-Pad21)") (class "Default")
      (node (ref "JP2") (pin "21") (pinfunction "21_21") (pintype "passive"))
    )
    (net (code "72") (name "unconnected-(JP2-Pad22)") (class "Default")
      (node (ref "JP2") (pin "22") (pinfunction "22_22") (pintype "passive"))
    )
    (net (code "73") (name "unconnected-(JP2-Pad23)") (class "Default")
      (node (ref "JP2") (pin "23") (pinfunction "23_23") (pintype "passive"))
    )
    (net (code "74") (name "unconnected-(JP2-Pad24)") (class "Default")
      (node (ref "JP2") (pin "24") (pinfunction "24_24") (pintype "passive"))
    )
    (net (code "75") (name "unconnected-(JP2-Pad26)") (class "Default")
      (node (ref "JP2") (pin "26") (pinfunction "26_26") (pintype "passive"))
    )
    (net (code "76") (name "unconnected-(JP2-Pad27)") (class "Default")
      (node (ref "JP2") (pin "27") (pinfunction "27_27") (pintype "passive"))
    )
    (net (code "77") (name "unconnected-(JP2-Pad28)") (class "Default")
      (node (ref "JP2") (pin "28") (pinfunction "28_28") (pintype "passive"))
    )
    (net (code "78") (name "unconnected-(JP2-Pad29)") (class "Default")
      (node (ref "JP2") (pin "29") (pinfunction "29_29") (pintype "passive"))
    )
    (net (code "79") (name "unconnected-(JP2-Pad31)") (class "Default")
      (node (ref "JP2") (pin "31") (pinfunction "31_31") (pintype "passive"))
    )
    (net (code "80") (name "unconnected-(JP2-Pad32)") (class "Default")
      (node (ref "JP2") (pin "32") (pinfunction "32_32") (pintype "passive"))
    )
    (net (code "81") (name "unconnected-(JP2-Pad33)") (class "Default")
      (node (ref "JP2") (pin "33") (pinfunction "33_33") (pintype "passive"))
    )
    (net (code "82") (name "unconnected-(JP2-Pad35)") (class "Default")
      (node (ref "JP2") (pin "35") (pinfunction "35_35") (pintype "passive"))
    )
    (net (code "83") (name "unconnected-(JP2-Pad37)") (class "Default")
      (node (ref "JP2") (pin "37") (pinfunction "37_37") (pintype "passive"))
    )
    (net (code "84") (name "unconnected-(JP2-Pad38)") (class "Default")
      (node (ref "JP2") (pin "38") (pinfunction "38_38") (pintype "passive"))
    )
    (net (code "85") (name "unconnected-(JP2-Pad40)") (class "Default")
      (node (ref "JP2") (pin "40") (pinfunction "40_40") (pintype "passive"))
    )
    (net (code "86") (name "unconnected-(OUTPUT_MODE-Pad1)") (class "Default")
      (node (ref "OUTPUT_MODE") (pin "1") (pinfunction "1_1") (pintype "passive"))
    )
    (net (code "87") (name "unconnected-(U$1-PadEXTINT)") (class "Default")
      (node (ref "U$1") (pin "EXTINT") (pinfunction "EXTINT_EXTINT") (pintype "bidirectional"))
    )
    (net (code "88") (name "unconnected-(U$1-PadLNA_EN)") (class "Default")
      (node (ref "U$1") (pin "LNA_EN") (pinfunction "LNA_EN_LNA_EN") (pintype "bidirectional"))
    )
    (net (code "89") (name "unconnected-(U$1-PadRESET_N)") (class "Default")
      (node (ref "U$1") (pin "RESET_N") (pinfunction "RESET_N_RESET_N") (pintype "bidirectional"))
    )
    (net (code "90") (name "unconnected-(U$1-PadSAFEBOOT_N)") (class "Default")
      (node (ref "U$1") (pin "SAFEBOOT_N") (pinfunction "SAFEBOOT_N_SAFEBOOT_N") (pintype "bidirectional"))
    )
    (net (code "91") (name "unconnected-(U$1-PadSCL)") (class "Default")
      (node (ref "U$1") (pin "SCL") (pinfunction "SCL_SCL") (pintype "bidirectional"))
    )
    (net (code "92") (name "unconnected-(U$1-PadSDA)") (class "Default")
      (node (ref "U$1") (pin "SDA") (pinfunction "SDA_SDA") (pintype "bidirectional"))
    )
    (net (code "93") (name "unconnected-(U$1-PadVIO_SEL)") (class "Default")
      (node (ref "U$1") (pin "VIO_SEL") (pinfunction "VIO_SEL_VIO_SEL") (pintype "bidirectional"))
    )
    (net (code "94") (name "unconnected-(U$2-RESET-Pad6)") (class "Default")
      (node (ref "U$2") (pin "6") (pinfunction "RESET_6") (pintype "bidirectional"))
    )
    (net (code "95") (name "unconnected-(U$4-NC$0-Pad1)") (class "Default")
      (node (ref "U$4") (pin "1") (pinfunction "NC$0_1") (pintype "bidirectional"))
    )
    (net (code "96") (name "unconnected-(U$4-NC$1-Pad2)") (class "Default")
      (node (ref "U$4") (pin "2") (pinfunction "NC$1_2") (pintype "bidirectional"))
    )
    (net (code "97") (name "unconnected-(U$4-NC$2-Pad7)") (class "Default")
      (node (ref "U$4") (pin "7") (pinfunction "NC$2_7") (pintype "bidirectional"))
    )
    (net (code "98") (name "unconnected-(U$4-NC$4-Pad12)") (class "Default")
      (node (ref "U$4") (pin "12") (pinfunction "NC$4_12") (pintype "bidirectional"))
    )
    (net (code "99") (name "unconnected-(U$4-NC$5-Pad14)") (class "Default")
      (node (ref "U$4") (pin "14") (pinfunction "NC$5_14") (pintype "bidirectional"))
    )
    (net (code "100") (name "unconnected-(U$4-RESET-Pad3)") (class "Default")
      (node (ref "U$4") (pin "3") (pinfunction "RESET_3") (pintype "bidirectional"))
    )
    (net (code "101") (name "unconnected-(U$4-RXB-Pad11)") (class "Default")
      (node (ref "U$4") (pin "11") (pinfunction "RXB_11") (pintype "bidirectional"))
    )
    (net (code "102") (name "unconnected-(U$4-WKUP-Pad6)") (class "Default")
      (node (ref "U$4") (pin "6") (pinfunction "WKUP_6") (pintype "bidirectional"))
    )
    (net (code "103") (name "unconnected-(U$8-PadPWRGD)") (class "Default")
      (node (ref "U$8") (pin "PWRGD") (pinfunction "PWRGD_PWRGD") (pintype "bidirectional"))
    )
    (net (code "104") (name "unconnected-(U1-CHR0-Pad15)") (class "Default")
      (node (ref "U1") (pin "15") (pinfunction "CHR0_15") (pintype "output"))
    )
    (net (code "105") (name "unconnected-(U1-CHR1-Pad14)") (class "Default")
      (node (ref "U1") (pin "14") (pinfunction "CHR1_14") (pintype "output"))
    )
    (net (code "106") (name "unconnected-(U1-CHREN-Pad13)") (class "Default")
      (node (ref "U1") (pin "13") (pinfunction "CHREN_13") (pintype "output"))
    )
    (net (code "107") (name "unconnected-(U1-CTS-Pad23)") (class "Default")
      (node (ref "U1") (pin "23") (pinfunction "CTS_23") (pintype "input"))
    )
    (net (code "108") (name "unconnected-(U1-DCD-Pad1)") (class "Default")
      (node (ref "U1") (pin "1") (pinfunction "DCD_1") (pintype "input"))
    )
    (net (code "109") (name "unconnected-(U1-DSR-Pad27)") (class "Default")
      (node (ref "U1") (pin "27") (pinfunction "DSR_27") (pintype "input"))
    )
    (net (code "110") (name "unconnected-(U1-DTR-Pad28)") (class "Default")
      (node (ref "U1") (pin "28") (pinfunction "DTR_28") (pintype "output"))
    )
    (net (code "111") (name "unconnected-(U1-GPIO.2{slash}RS485-Pad17)") (class "Default")
      (node (ref "U1") (pin "17") (pinfunction "GPIO.2/RS485_17") (pintype "bidirectional"))
    )
    (net (code "112") (name "unconnected-(U1-GPIO.3{slash}WAKEUP-Pad16)") (class "Default")
      (node (ref "U1") (pin "16") (pinfunction "GPIO.3/WAKEUP_16") (pintype "bidirectional"))
    )
    (net (code "113") (name "unconnected-(U1-GPIO.4-Pad22)") (class "Default")
      (node (ref "U1") (pin "22") (pinfunction "GPIO.4_22") (pintype "bidirectional"))
    )
    (net (code "114") (name "unconnected-(U1-GPIO.5-Pad21)") (class "Default")
      (node (ref "U1") (pin "21") (pinfunction "GPIO.5_21") (pintype "bidirectional"))
    )
    (net (code "115") (name "unconnected-(U1-GPIO.6-Pad20)") (class "Default")
      (node (ref "U1") (pin "20") (pinfunction "GPIO.6_20") (pintype "bidirectional"))
    )
    (net (code "116") (name "unconnected-(U1-NC-Pad10)") (class "Default")
      (node (ref "U1") (pin "10") (pinfunction "NC_10") (pintype "no_connect"))
    )
    (net (code "117") (name "unconnected-(U1-RI{slash}CLK-Pad2)") (class "Default")
      (node (ref "U1") (pin "2") (pinfunction "RI/CLK_2") (pintype "bidirectional"))
    )
    (net (code "118") (name "unconnected-(U1-RTS-Pad24)") (class "Default")
      (node (ref "U1") (pin "24") (pinfunction "RTS_24") (pintype "output"))
    )
    (net (code "119") (name "unconnected-(U1-SUSPEND-Pad12)") (class "Default")
      (node (ref "U1") (pin "12") (pinfunction "SUSPEND_12") (pintype "output"))
    )
  )
)
